# Main_EDA_-.net
KiCad netlist of a schematic drawn in Altium Designer
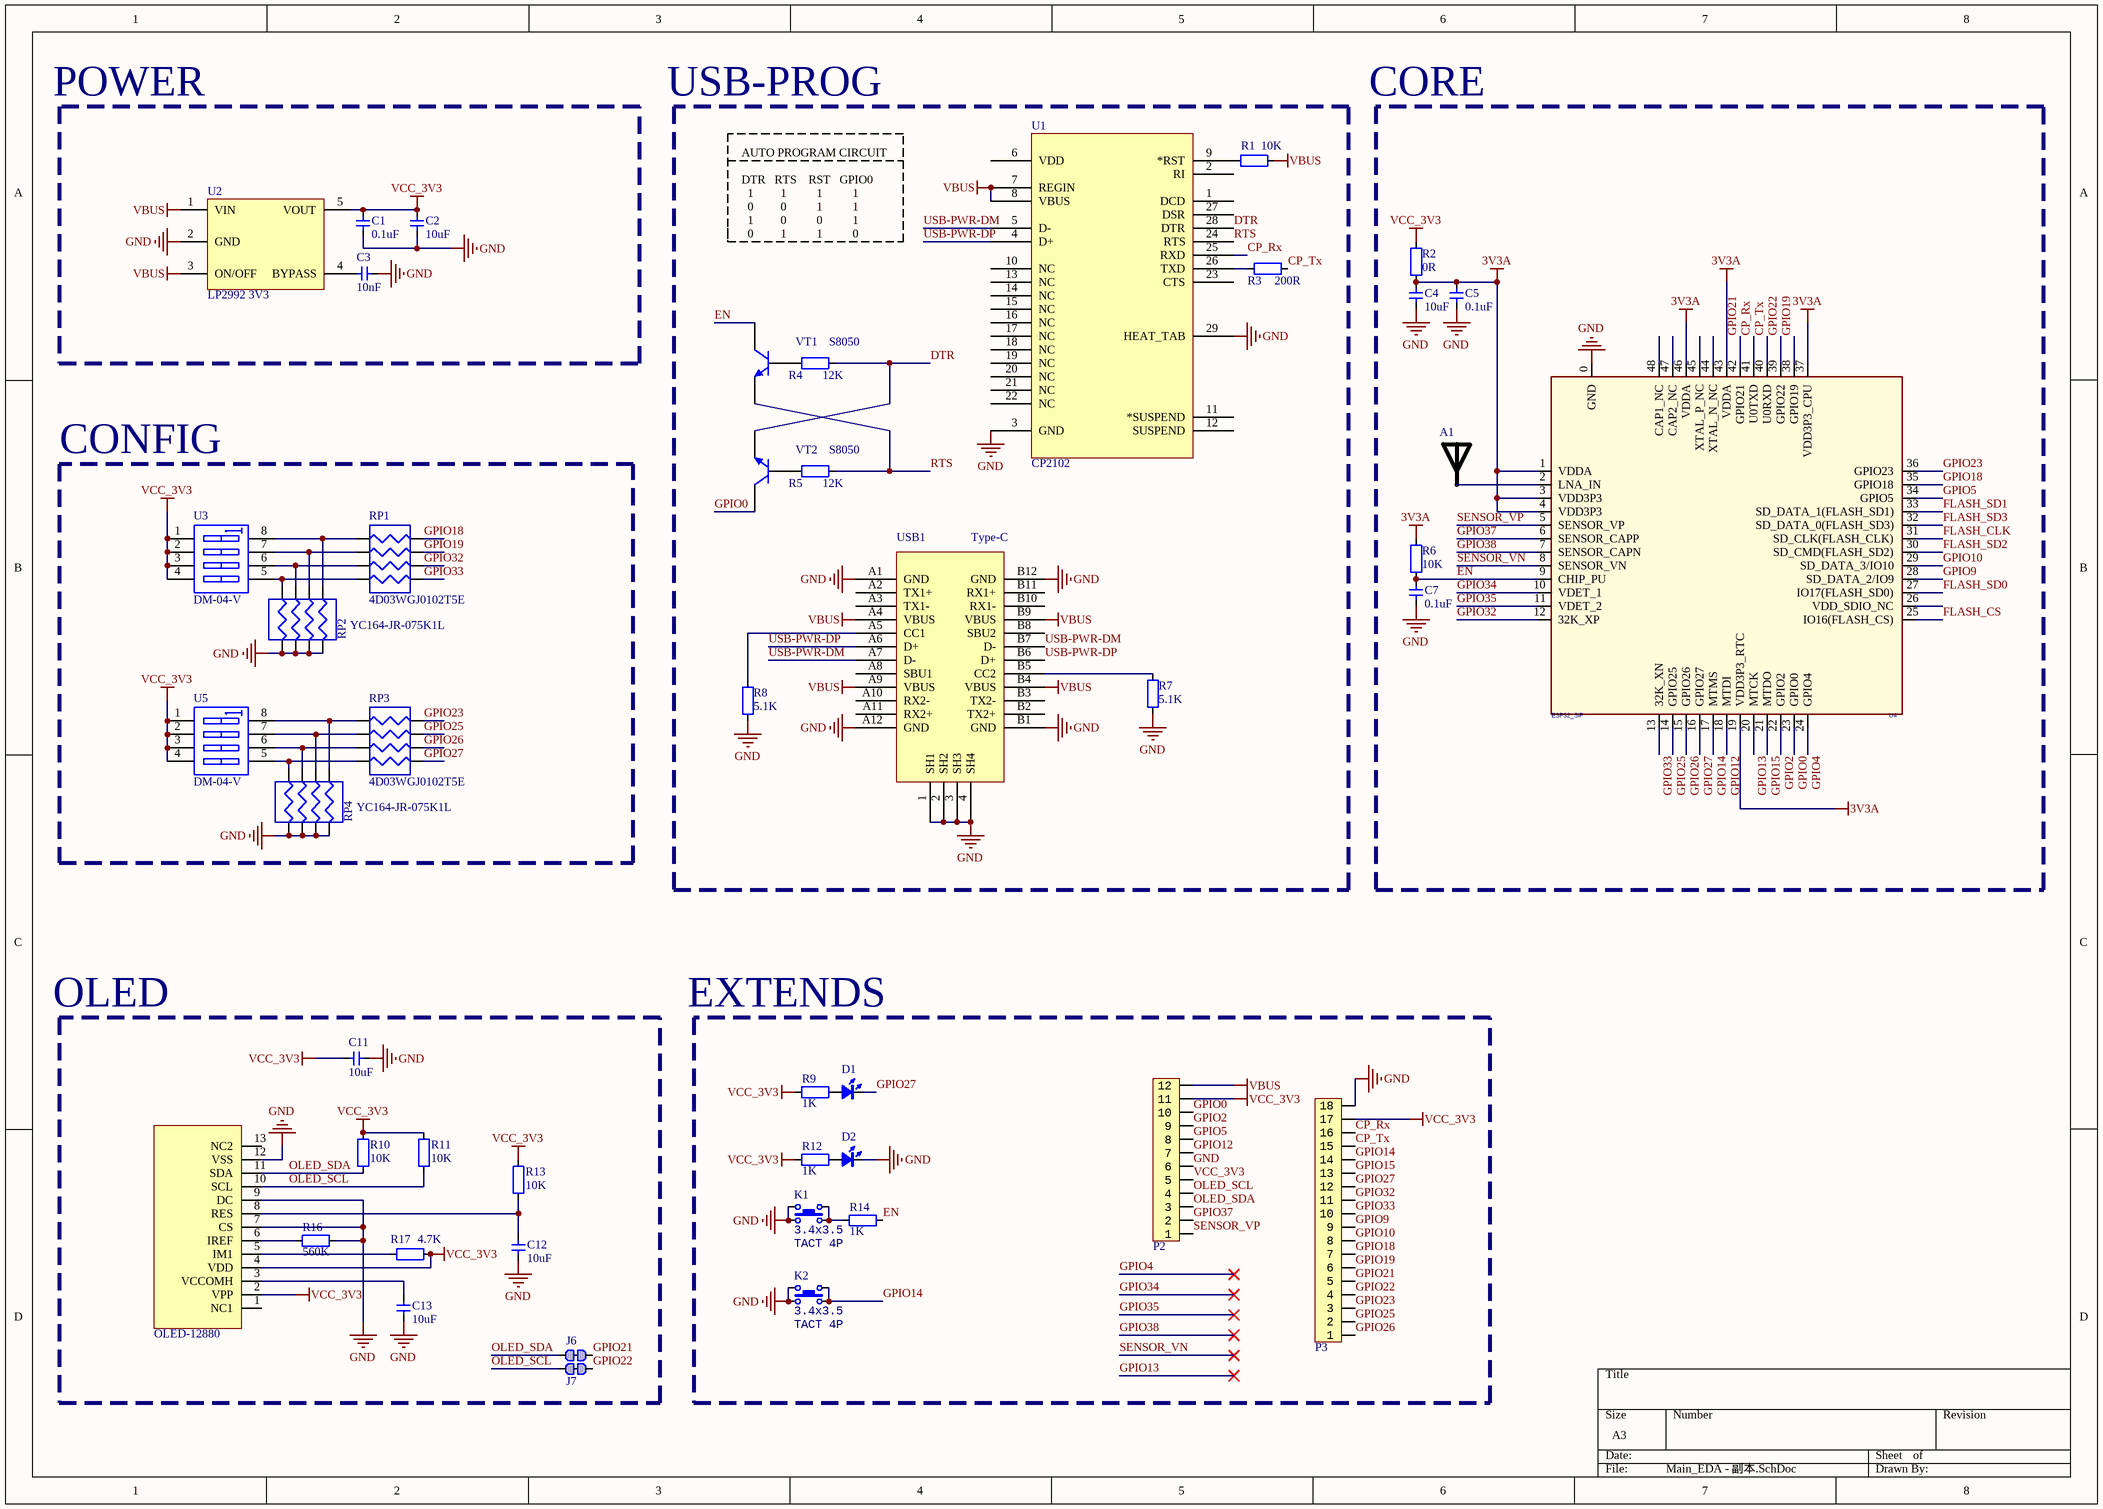
[diagram p0: Main_EDA - 副本.SchDoc]

(export (version "E")
  (design (tool "Eeschema 10.0.6"))
  (components
    (comp (ref "1")
      (value "OLED-12880")
      (footprint "OLED-12880")
      (libsource (lib "mLib") (part "OLED-12880"))
    )
    (comp (ref "A1")
      (value "RAINSUN")
      (footprint "ANT-Rainsun-AN5120")
      (libsource (lib "MyPcbLib") (part "ANT-Rainsun-AP5120"))
    )
    (comp (ref "C1")
      (value "0.1uF")
      (footprint "CAP_0402")
      (description "Capacitor")
      (libsource (lib "MyPcbLib") (part "电容-0402"))
    )
    (comp (ref "C2")
      (value "10uF")
      (footprint "CAP_0402")
      (description "Capacitor")
      (libsource (lib "MyPcbLib") (part "电容-0402"))
    )
    (comp (ref "C3")
      (value "10nF")
      (footprint "CAP_0402")
      (description "Capacitor")
      (libsource (lib "MyPcbLib") (part "电容-0402"))
    )
    (comp (ref "C4")
      (value "10uF")
      (footprint "CAP_0402")
      (description "Capacitor")
      (libsource (lib "MyPcbLib") (part "电容-0402"))
    )
    (comp (ref "C5")
      (value "0.1uF")
      (footprint "CAP_0402")
      (description "Capacitor")
      (libsource (lib "MyPcbLib") (part "电容-0402"))
    )
    (comp (ref "C7")
      (value "0.1uF")
      (footprint "CAP_0402")
      (description "Capacitor")
      (libsource (lib "MyPcbLib") (part "电容-0402"))
    )
    (comp (ref "C11")
      (value "10uF")
      (footprint "CAP_0402")
      (description "Capacitor")
      (libsource (lib "MyPcbLib") (part "电容-0402"))
    )
    (comp (ref "C12")
      (value "10uF")
      (footprint "CAP_0402")
      (description "Capacitor")
      (libsource (lib "MyPcbLib") (part "电容-0402"))
    )
    (comp (ref "C13")
      (value "10uF")
      (footprint "CAP_0402")
      (description "Capacitor")
      (libsource (lib "MyPcbLib") (part "电容-0402"))
    )
    (comp (ref "D1")
      (value "color?")
      (footprint "LED_0402_RED")
      (description "LED")
      (libsource (lib "KitSprout") (part "LED_0402"))
    )
    (comp (ref "D2")
      (value "color?")
      (footprint "LED_0402_RED")
      (description "LED")
      (libsource (lib "KitSprout") (part "LED_0402"))
    )
    (comp (ref "J6")
      (value "跳线")
      (footprint "0402-0R")
      (description "Resistor")
      (fields (field (name "PUBLISHER") "Altium Limited"))
      (libsource (lib "MyPcbLib") (part "跳线"))
    )
    (comp (ref "J7")
      (value "跳线")
      (footprint "0402-0R")
      (description "Resistor")
      (fields (field (name "PUBLISHER") "Altium Limited"))
      (libsource (lib "MyPcbLib") (part "跳线"))
    )
    (comp (ref "K1")
      (value "3.4x3.5")
      (footprint "ButtonTACT_3.5*3.55_90")
      (description "Button")
      (fields (field (name "TYPE") "TACT 4P") (field (name "Comment") "TACT 4P"))
      (libsource (lib "KitSprout") (part "ButtonTACT"))
    )
    (comp (ref "K2")
      (value "3.4x3.5")
      (footprint "ButtonTACT_3.5*3.55_90")
      (description "Button")
      (fields (field (name "TYPE") "TACT 4P") (field (name "Comment") "TACT 4P"))
      (libsource (lib "KitSprout") (part "ButtonTACT"))
    )
    (comp (ref "P2")
      (value "HDR1x12_2.54")
      (footprint "HDR1X12_2.54_180")
      (description "Header")
      (libsource (lib "KitSprout") (part "HDR1x12_2.54"))
    )
    (comp (ref "P3")
      (value "HDR1x18_2.54")
      (footprint "HDR1X18_2.54_180")
      (description "Header")
      (libsource (lib "KitSprout") (part "HDR1x18_2.54"))
    )
    (comp (ref "R1")
      (value "10K")
      (footprint "RES_0402")
      (description "Resistor")
      (libsource (lib "") (part "电阻-0402_3"))
    )
    (comp (ref "R2")
      (value "0R")
      (footprint "RES_0402")
      (description "Resistor")
      (libsource (lib "") (part "电阻-0402_1"))
    )
    (comp (ref "R3")
      (value "200R")
      (footprint "RES_0402")
      (description "Resistor")
      (libsource (lib "") (part "电阻-0402_3"))
    )
    (comp (ref "R4")
      (value "12K")
      (footprint "RES_0402")
      (description "Resistor")
      (libsource (lib "") (part "电阻-0402_3"))
    )
    (comp (ref "R5")
      (value "12K")
      (footprint "RES_0402")
      (description "Resistor")
      (libsource (lib "") (part "电阻-0402_3"))
    )
    (comp (ref "R6")
      (value "10K")
      (footprint "RES_0402")
      (description "Resistor")
      (libsource (lib "") (part "电阻-0402_1"))
    )
    (comp (ref "R7")
      (value "5.1K")
      (footprint "RES_0402")
      (description "Resistor")
      (libsource (lib "") (part "电阻-0402_1"))
    )
    (comp (ref "R8")
      (value "5.1K")
      (footprint "RES_0402")
      (description "Resistor")
      (libsource (lib "") (part "电阻-0402_1"))
    )
    (comp (ref "R9")
      (value "1K")
      (footprint "RES_0402")
      (description "Resistor")
      (libsource (lib "") (part "电阻-0402_2"))
    )
    (comp (ref "R10")
      (value "10K")
      (footprint "RES_0402")
      (description "Resistor")
      (libsource (lib "MyPcbLib") (part "电阻-0402"))
    )
    (comp (ref "R11")
      (value "10K")
      (footprint "RES_0402")
      (description "Resistor")
      (libsource (lib "MyPcbLib") (part "电阻-0402"))
    )
    (comp (ref "R12")
      (value "1K")
      (footprint "RES_0402")
      (description "Resistor")
      (libsource (lib "") (part "电阻-0402_2"))
    )
    (comp (ref "R13")
      (value "10K")
      (footprint "RES_0402")
      (description "Resistor")
      (libsource (lib "MyPcbLib") (part "电阻-0402"))
    )
    (comp (ref "R14")
      (value "1K")
      (footprint "RES_0402")
      (description "Resistor")
      (libsource (lib "") (part "电阻-0402_2"))
    )
    (comp (ref "R16")
      (value "560K")
      (footprint "RES_0402")
      (description "Resistor")
      (libsource (lib "") (part "电阻-0402_2"))
    )
    (comp (ref "R17")
      (value "4.7K")
      (footprint "RES_0402")
      (description "Resistor")
      (libsource (lib "") (part "电阻-0402_2"))
    )
    (comp (ref "RP1")
      (value "4D03WGJ0102T5E")
      (footprint "RES-ARRAY-SMD_0603-8P-L3.2-W1.6-BL")
      (libsource (lib "Schlib1") (part "RP"))
    )
    (comp (ref "RP2")
      (value "YC164-JR-075K1L")
      (footprint "RES-ARRAY-SMD_0603-8P-L3.2-W1.6-BL")
      (libsource (lib "Schlib1") (part "RP"))
    )
    (comp (ref "RP3")
      (value "4D03WGJ0102T5E")
      (footprint "RES-ARRAY-SMD_0603-8P-L3.2-W1.6-BL")
      (libsource (lib "Schlib1") (part "RP"))
    )
    (comp (ref "RP4")
      (value "YC164-JR-075K1L")
      (footprint "RES-ARRAY-SMD_0603-8P-L3.2-W1.6-BL")
      (libsource (lib "Schlib1") (part "RP"))
    )
    (comp (ref "U1")
      (value "CP2102")
      (footprint "QFN-28")
      (description "USB转TTL")
      (libsource (lib "mLib") (part "CP2102"))
    )
    (comp (ref "U2")
      (value "LP2992 3V3")
      (footprint "SOT23-5")
      (description "LDO")
      (libsource (lib "MyPcbLib") (part "LP2992"))
    )
    (comp (ref "U3")
      (value "DM-04-V")
      (footprint "SW-SMD_8P-L11.1-W6.2-P2.54-LS9.8")
      (description "DIP Switch, 4 Position, SPST")
      (fields (field (name "PUBLISHER") "Altium Limited"))
      (libsource (lib "Miscellaneous Devices") (part "SW DIP-4"))
    )
    (comp (ref "U4")
      (value "ESP32_SIP")
      (footprint "QFN-48_7X7")
      (libsource (lib "MyPcbLib") (part "ESP32-PICO"))
    )
    (comp (ref "U5")
      (value "DM-04-V")
      (footprint "SW-SMD_8P-L11.1-W6.2-P2.54-LS9.8")
      (description "DIP Switch, 4 Position, SPST")
      (fields (field (name "PUBLISHER") "Altium Limited"))
      (libsource (lib "Miscellaneous Devices") (part "SW DIP-4"))
    )
    (comp (ref "USB1")
      (value "Type-C")
      (footprint "Type-C-TOP")
      (libsource (lib "MyPcbLib") (part "USB-Type-C-TOP"))
    )
    (comp (ref "VT1")
      (value "S8050")
      (footprint "SMT_TRIODE_NPN")
      (description "Surface mount NPN transistor, package SOT-23")
      (libsource (lib "MyPcbLib") (part "SMT_TRIODE_NPN"))
    )
    (comp (ref "VT2")
      (value "S8050")
      (footprint "SMT_TRIODE_NPN")
      (description "Surface mount NPN transistor, package SOT-23")
      (libsource (lib "MyPcbLib") (part "SMT_TRIODE_NPN"))
    )
  )
  (nets
    (net (code "1") (name "/CP_Rx") (class "Default")
      (node (ref "P3") (pin "16") (pinfunction "16_16") (pintype "passive"))
      (node (ref "U1") (pin "25") (pinfunction "RXD_25") (pintype "passive"))
      (node (ref "U4") (pin "41") (pinfunction "U0TXD_41") (pintype "power_in"))
    )
    (net (code "2") (name "/CP_Tx") (class "Default")
      (node (ref "P3") (pin "15") (pinfunction "15_15") (pintype "passive"))
      (node (ref "R3") (pin "1") (pinfunction "1_1") (pintype "passive"))
      (node (ref "U4") (pin "40") (pinfunction "U0RXD_40") (pintype "power_in"))
    )
    (net (code "3") (name "/DTR") (class "Default")
      (node (ref "R4") (pin "1") (pinfunction "1_1") (pintype "passive"))
      (node (ref "U1") (pin "28") (pinfunction "DTR_28") (pintype "passive"))
      (node (ref "VT2") (pin "2") (pinfunction "E_2") (pintype "passive"))
    )
    (net (code "4") (name "/EN") (class "Default")
      (node (ref "C7") (pin "1") (pinfunction "1_1") (pintype "passive"))
      (node (ref "R14") (pin "2") (pinfunction "2_2") (pintype "passive"))
      (node (ref "R6") (pin "2") (pinfunction "2_2") (pintype "passive"))
      (node (ref "U4") (pin "9") (pinfunction "CHIP_PU_9") (pintype "passive"))
      (node (ref "VT1") (pin "3") (pinfunction "C_3") (pintype "passive"))
    )
    (net (code "5") (name "/FLASH_CLK") (class "Default")
      (node (ref "U4") (pin "31") (pinfunction "SD_CLK(FLASH_CLK)_31") (pintype "passive"))
    )
    (net (code "6") (name "/FLASH_CS") (class "Default")
      (node (ref "U4") (pin "25") (pinfunction "IO16(FLASH_CS)_25") (pintype "passive"))
    )
    (net (code "7") (name "/FLASH_SD0") (class "Default")
      (node (ref "U4") (pin "27") (pinfunction "IO17(FLASH_SD0)_27") (pintype "passive"))
    )
    (net (code "8") (name "/FLASH_SD1") (class "Default")
      (node (ref "U4") (pin "33") (pinfunction "SD_DATA_1(FLASH_SD1)_33") (pintype "passive"))
    )
    (net (code "9") (name "/FLASH_SD2") (class "Default")
      (node (ref "U4") (pin "30") (pinfunction "SD_CMD(FLASH_SD2)_30") (pintype "passive"))
    )
    (net (code "10") (name "/FLASH_SD3") (class "Default")
      (node (ref "U4") (pin "32") (pinfunction "SD_DATA_0(FLASH_SD3)_32") (pintype "passive"))
    )
    (net (code "11") (name "/GPIO0") (class "Default")
      (node (ref "P2") (pin "10") (pinfunction "10_10") (pintype "passive"))
      (node (ref "U4") (pin "23") (pinfunction "GPIO0_23") (pintype "passive"))
      (node (ref "VT2") (pin "3") (pinfunction "C_3") (pintype "passive"))
    )
    (net (code "12") (name "/GPIO2") (class "Default")
      (node (ref "P2") (pin "9") (pinfunction "9_9") (pintype "passive"))
      (node (ref "U4") (pin "22") (pinfunction "GPIO2_22") (pintype "passive"))
    )
    (net (code "13") (name "/GPIO4") (class "Default")
      (node (ref "U4") (pin "24") (pinfunction "GPIO4_24") (pintype "passive+no_connect"))
    )
    (net (code "14") (name "/GPIO5") (class "Default")
      (node (ref "P2") (pin "8") (pinfunction "8_8") (pintype "passive"))
      (node (ref "U4") (pin "34") (pinfunction "GPIO5_34") (pintype "passive"))
    )
    (net (code "15") (name "/GPIO9") (class "Default")
      (node (ref "P3") (pin "9") (pinfunction "9_9") (pintype "passive"))
      (node (ref "U4") (pin "28") (pinfunction "SD_DATA_2/IO9_28") (pintype "passive"))
    )
    (net (code "16") (name "/GPIO10") (class "Default")
      (node (ref "P3") (pin "8") (pinfunction "8_8") (pintype "passive"))
      (node (ref "U4") (pin "29") (pinfunction "SD_DATA_3/IO10_29") (pintype "passive"))
    )
    (net (code "17") (name "/GPIO12") (class "Default")
      (node (ref "P2") (pin "7") (pinfunction "7_7") (pintype "passive"))
      (node (ref "U4") (pin "18") (pinfunction "MTDI_18") (pintype "passive"))
    )
    (net (code "18") (name "/GPIO13") (class "Default")
      (node (ref "U4") (pin "20") (pinfunction "MTCK_20") (pintype "passive+no_connect"))
    )
    (net (code "19") (name "/GPIO14") (class "Default")
      (node (ref "K2") (pin "2") (pinfunction "2_2") (pintype "passive"))
      (node (ref "K2") (pin "4") (pinfunction "4_4") (pintype "passive"))
      (node (ref "P3") (pin "14") (pinfunction "14_14") (pintype "passive"))
      (node (ref "U4") (pin "17") (pinfunction "MTMS_17") (pintype "passive"))
    )
    (net (code "20") (name "/GPIO15") (class "Default")
      (node (ref "P3") (pin "13") (pinfunction "13_13") (pintype "passive"))
      (node (ref "U4") (pin "21") (pinfunction "MTDO_21") (pintype "passive"))
    )
    (net (code "21") (name "/GPIO18") (class "Default")
      (node (ref "P3") (pin "7") (pinfunction "7_7") (pintype "passive"))
      (node (ref "RP1") (pin "8") (pinfunction "8_8") (pintype "passive"))
      (node (ref "U4") (pin "35") (pinfunction "GPIO18_35") (pintype "passive"))
    )
    (net (code "22") (name "/GPIO19") (class "Default")
      (node (ref "P3") (pin "6") (pinfunction "6_6") (pintype "passive"))
      (node (ref "RP1") (pin "7") (pinfunction "7_7") (pintype "passive"))
      (node (ref "U4") (pin "38") (pinfunction "GPIO19_38") (pintype "passive"))
    )
    (net (code "23") (name "/GPIO21") (class "Default")
      (node (ref "J6") (pin "2") (pinfunction "2_2") (pintype "passive"))
      (node (ref "P3") (pin "5") (pinfunction "5_5") (pintype "passive"))
      (node (ref "U4") (pin "42") (pinfunction "GPIO21_42") (pintype "passive"))
    )
    (net (code "24") (name "/GPIO22") (class "Default")
      (node (ref "J7") (pin "2") (pinfunction "2_2") (pintype "passive"))
      (node (ref "P3") (pin "4") (pinfunction "4_4") (pintype "passive"))
      (node (ref "U4") (pin "39") (pinfunction "GPIO22_39") (pintype "passive"))
    )
    (net (code "25") (name "/GPIO23") (class "Default")
      (node (ref "P3") (pin "3") (pinfunction "3_3") (pintype "passive"))
      (node (ref "RP3") (pin "8") (pinfunction "8_8") (pintype "passive"))
      (node (ref "U4") (pin "36") (pinfunction "GPIO23_36") (pintype "passive"))
    )
    (net (code "26") (name "/GPIO25") (class "Default")
      (node (ref "P3") (pin "2") (pinfunction "2_2") (pintype "passive"))
      (node (ref "RP3") (pin "7") (pinfunction "7_7") (pintype "passive"))
      (node (ref "U4") (pin "14") (pinfunction "GPIO25_14") (pintype "passive"))
    )
    (net (code "27") (name "/GPIO26") (class "Default")
      (node (ref "P3") (pin "1") (pinfunction "1_1") (pintype "passive"))
      (node (ref "RP3") (pin "6") (pinfunction "6_6") (pintype "passive"))
      (node (ref "U4") (pin "15") (pinfunction "GPIO26_15") (pintype "passive"))
    )
    (net (code "28") (name "/GPIO27") (class "Default")
      (node (ref "D1") (pin "2") (pinfunction "K_2") (pintype "passive"))
      (node (ref "P3") (pin "12") (pinfunction "12_12") (pintype "passive"))
      (node (ref "RP3") (pin "5") (pinfunction "5_5") (pintype "passive"))
      (node (ref "U4") (pin "16") (pinfunction "GPIO27_16") (pintype "passive"))
    )
    (net (code "29") (name "/GPIO32") (class "Default")
      (node (ref "P3") (pin "11") (pinfunction "11_11") (pintype "passive"))
      (node (ref "RP1") (pin "6") (pinfunction "6_6") (pintype "passive"))
      (node (ref "U4") (pin "12") (pinfunction "32K_XP_12") (pintype "passive"))
    )
    (net (code "30") (name "/GPIO33") (class "Default")
      (node (ref "P3") (pin "10") (pinfunction "10_10") (pintype "passive"))
      (node (ref "RP1") (pin "5") (pinfunction "5_5") (pintype "passive"))
      (node (ref "U4") (pin "13") (pinfunction "32K_XN_13") (pintype "passive"))
    )
    (net (code "31") (name "/GPIO34") (class "Default")
      (node (ref "U4") (pin "10") (pinfunction "VDET_1_10") (pintype "passive+no_connect"))
    )
    (net (code "32") (name "/GPIO35") (class "Default")
      (node (ref "U4") (pin "11") (pinfunction "VDET_2_11") (pintype "passive+no_connect"))
    )
    (net (code "33") (name "/GPIO37") (class "Default")
      (node (ref "P2") (pin "2") (pinfunction "2_2") (pintype "passive"))
      (node (ref "U4") (pin "6") (pinfunction "SENSOR_CAPP_6") (pintype "passive"))
    )
    (net (code "34") (name "/GPIO38") (class "Default")
      (node (ref "U4") (pin "7") (pinfunction "SENSOR_CAPN_7") (pintype "passive+no_connect"))
    )
    (net (code "35") (name "/OLED_SCL") (class "Default")
      (node (ref "1") (pin "10") (pinfunction "SCL_10") (pintype "passive"))
      (node (ref "J7") (pin "1") (pinfunction "1_1") (pintype "passive"))
      (node (ref "P2") (pin "4") (pinfunction "4_4") (pintype "passive"))
      (node (ref "R11") (pin "1") (pinfunction "1_1") (pintype "passive"))
    )
    (net (code "36") (name "/OLED_SDA") (class "Default")
      (node (ref "1") (pin "11") (pinfunction "SDA_11") (pintype "passive"))
      (node (ref "J6") (pin "1") (pinfunction "1_1") (pintype "passive"))
      (node (ref "P2") (pin "3") (pinfunction "3_3") (pintype "passive"))
      (node (ref "R10") (pin "1") (pinfunction "1_1") (pintype "passive"))
    )
    (net (code "37") (name "/RTS") (class "Default")
      (node (ref "R5") (pin "1") (pinfunction "1_1") (pintype "passive"))
      (node (ref "U1") (pin "24") (pinfunction "RTS_24") (pintype "passive"))
      (node (ref "VT1") (pin "2") (pinfunction "E_2") (pintype "passive"))
    )
    (net (code "38") (name "/SENSOR_VN") (class "Default")
      (node (ref "U4") (pin "8") (pinfunction "SENSOR_VN_8") (pintype "passive+no_connect"))
    )
    (net (code "39") (name "/SENSOR_VP") (class "Default")
      (node (ref "P2") (pin "1") (pinfunction "1_1") (pintype "passive"))
      (node (ref "U4") (pin "5") (pinfunction "SENSOR_VP_5") (pintype "passive"))
    )
    (net (code "40") (name "/USB-PWR-DM") (class "Default")
      (node (ref "U1") (pin "5") (pinfunction "D-_5") (pintype "passive"))
      (node (ref "USB1") (pin "A7") (pinfunction "D-_A7") (pintype "passive"))
      (node (ref "USB1") (pin "B7") (pinfunction "D-_B7") (pintype "passive"))
    )
    (net (code "41") (name "/USB-PWR-DP") (class "Default")
      (node (ref "U1") (pin "4") (pinfunction "D+_4") (pintype "passive"))
      (node (ref "USB1") (pin "A6") (pinfunction "D+_A6") (pintype "passive"))
      (node (ref "USB1") (pin "B6") (pinfunction "D+_B6") (pintype "passive"))
    )
    (net (code "42") (name "3V3A") (class "Default")
      (node (ref "C4") (pin "2") (pinfunction "2_2") (pintype "passive"))
      (node (ref "C5") (pin "2") (pinfunction "2_2") (pintype "passive"))
      (node (ref "R2") (pin "2") (pinfunction "2_2") (pintype "passive"))
      (node (ref "R6") (pin "1") (pinfunction "1_1") (pintype "passive"))
      (node (ref "U4") (pin "1") (pinfunction "VDDA_1") (pintype "power_in"))
      (node (ref "U4") (pin "19") (pinfunction "VDD3P3_RTC_19") (pintype "power_in"))
      (node (ref "U4") (pin "3") (pinfunction "VDD3P3_3") (pintype "power_in"))
      (node (ref "U4") (pin "37") (pinfunction "VDD3P3_CPU_37") (pintype "power_in"))
      (node (ref "U4") (pin "4") (pinfunction "VDD3P3_4") (pintype "power_in"))
      (node (ref "U4") (pin "43") (pinfunction "VDDA_43") (pintype "power_in"))
      (node (ref "U4") (pin "46") (pinfunction "VDDA_46") (pintype "power_in"))
    )
    (net (code "43") (name "GND") (class "Default")
      (node (ref "1") (pin "12") (pinfunction "VSS_12") (pintype "passive"))
      (node (ref "1") (pin "7") (pinfunction "CS_7") (pintype "passive"))
      (node (ref "1") (pin "9") (pinfunction "DC_9") (pintype "passive"))
      (node (ref "C1") (pin "1") (pinfunction "1_1") (pintype "passive"))
      (node (ref "C11") (pin "1") (pinfunction "1_1") (pintype "passive"))
      (node (ref "C12") (pin "1") (pinfunction "1_1") (pintype "passive"))
      (node (ref "C13") (pin "1") (pinfunction "1_1") (pintype "passive"))
      (node (ref "C2") (pin "1") (pinfunction "1_1") (pintype "passive"))
      (node (ref "C3") (pin "1") (pinfunction "1_1") (pintype "passive"))
      (node (ref "C4") (pin "1") (pinfunction "1_1") (pintype "passive"))
      (node (ref "C5") (pin "1") (pinfunction "1_1") (pintype "passive"))
      (node (ref "C7") (pin "2") (pinfunction "2_2") (pintype "passive"))
      (node (ref "D2") (pin "2") (pinfunction "K_2") (pintype "passive"))
      (node (ref "K1") (pin "1") (pinfunction "1_1") (pintype "passive"))
      (node (ref "K1") (pin "3") (pinfunction "3_3") (pintype "passive"))
      (node (ref "K2") (pin "1") (pinfunction "1_1") (pintype "passive"))
      (node (ref "K2") (pin "3") (pinfunction "3_3") (pintype "passive"))
      (node (ref "P2") (pin "6") (pinfunction "6_6") (pintype "passive"))
      (node (ref "P3") (pin "18") (pinfunction "18_18") (pintype "passive"))
      (node (ref "R16") (pin "2") (pinfunction "2_2") (pintype "passive"))
      (node (ref "R7") (pin "2") (pinfunction "2_2") (pintype "passive"))
      (node (ref "R8") (pin "2") (pinfunction "2_2") (pintype "passive"))
      (node (ref "RP2") (pin "5") (pinfunction "5_5") (pintype "passive"))
      (node (ref "RP2") (pin "6") (pinfunction "6_6") (pintype "passive"))
      (node (ref "RP2") (pin "7") (pinfunction "7_7") (pintype "passive"))
      (node (ref "RP2") (pin "8") (pinfunction "8_8") (pintype "passive"))
      (node (ref "RP4") (pin "5") (pinfunction "5_5") (pintype "passive"))
      (node (ref "RP4") (pin "6") (pinfunction "6_6") (pintype "passive"))
      (node (ref "RP4") (pin "7") (pinfunction "7_7") (pintype "passive"))
      (node (ref "RP4") (pin "8") (pinfunction "8_8") (pintype "passive"))
      (node (ref "U1") (pin "29") (pinfunction "HEAT_TAB_29") (pintype "passive"))
      (node (ref "U1") (pin "3") (pinfunction "GND_3") (pintype "passive"))
      (node (ref "U2") (pin "2") (pinfunction "GND_2") (pintype "passive"))
      (node (ref "U4") (pin "0") (pinfunction "GND_0") (pintype "power_in"))
      (node (ref "USB1") (pin "1") (pinfunction "SH1_1") (pintype "passive"))
      (node (ref "USB1") (pin "2") (pinfunction "SH2_2") (pintype "passive"))
      (node (ref "USB1") (pin "3") (pinfunction "SH3_3") (pintype "passive"))
      (node (ref "USB1") (pin "4") (pinfunction "SH4_4") (pintype "passive"))
      (node (ref "USB1") (pin "A1") (pinfunction "GND_A1") (pintype "passive"))
      (node (ref "USB1") (pin "A12") (pinfunction "GND_A12") (pintype "passive"))
      (node (ref "USB1") (pin "B1") (pinfunction "GND_B1") (pintype "passive"))
      (node (ref "USB1") (pin "B12") (pinfunction "GND_B12") (pintype "passive"))
    )
    (net (code "44") (name "Net-(1-IM1)") (class "Default")
      (node (ref "1") (pin "5") (pinfunction "IM1_5") (pintype "passive"))
      (node (ref "R17") (pin "1") (pinfunction "1_1") (pintype "passive"))
    )
    (net (code "45") (name "Net-(1-IREF)") (class "Default")
      (node (ref "1") (pin "6") (pinfunction "IREF_6") (pintype "passive"))
      (node (ref "R16") (pin "1") (pinfunction "1_1") (pintype "passive"))
    )
    (net (code "46") (name "Net-(1-RES)") (class "Default")
      (node (ref "1") (pin "8") (pinfunction "RES_8") (pintype "passive"))
      (node (ref "C12") (pin "2") (pinfunction "2_2") (pintype "passive"))
      (node (ref "R13") (pin "1") (pinfunction "1_1") (pintype "passive"))
    )
    (net (code "47") (name "Net-(1-VCCOMH)") (class "Default")
      (node (ref "1") (pin "3") (pinfunction "VCCOMH_3") (pintype "passive"))
      (node (ref "C13") (pin "2") (pinfunction "2_2") (pintype "passive"))
    )
    (net (code "48") (name "Net-(D1-A)") (class "Default")
      (node (ref "D1") (pin "1") (pinfunction "A_1") (pintype "passive"))
      (node (ref "R9") (pin "2") (pinfunction "2_2") (pintype "passive"))
    )
    (net (code "49") (name "Net-(D2-A)") (class "Default")
      (node (ref "D2") (pin "1") (pinfunction "A_1") (pintype "passive"))
      (node (ref "R12") (pin "2") (pinfunction "2_2") (pintype "passive"))
    )
    (net (code "50") (name "Net-(K1-Pad2)") (class "Default")
      (node (ref "K1") (pin "2") (pinfunction "2_2") (pintype "passive"))
      (node (ref "K1") (pin "4") (pinfunction "4_4") (pintype "passive"))
      (node (ref "R14") (pin "1") (pinfunction "1_1") (pintype "passive"))
    )
    (net (code "51") (name "Net-(U1-*RST)") (class "Default")
      (node (ref "R1") (pin "2") (pinfunction "2_2") (pintype "passive"))
      (node (ref "U1") (pin "9") (pinfunction "*RST_9") (pintype "passive"))
    )
    (net (code "52") (name "Net-(U1-TXD)") (class "Default")
      (node (ref "R3") (pin "2") (pinfunction "2_2") (pintype "passive"))
      (node (ref "U1") (pin "26") (pinfunction "TXD_26") (pintype "passive"))
    )
    (net (code "53") (name "Net-(U2-BYPASS)") (class "Default")
      (node (ref "C3") (pin "2") (pinfunction "2_2") (pintype "passive"))
      (node (ref "U2") (pin "4") (pinfunction "BYPASS_4") (pintype "passive"))
    )
    (net (code "54") (name "Net-(U3-B1)") (class "Default")
      (node (ref "RP1") (pin "1") (pinfunction "1_1") (pintype "passive"))
      (node (ref "RP2") (pin "1") (pinfunction "1_1") (pintype "passive"))
      (node (ref "U3") (pin "8") (pinfunction "B1_8") (pintype "passive"))
    )
    (net (code "55") (name "Net-(U3-B2)") (class "Default")
      (node (ref "RP1") (pin "2") (pinfunction "2_2") (pintype "passive"))
      (node (ref "RP2") (pin "2") (pinfunction "2_2") (pintype "passive"))
      (node (ref "U3") (pin "7") (pinfunction "B2_7") (pintype "passive"))
    )
    (net (code "56") (name "Net-(U3-B3)") (class "Default")
      (node (ref "RP1") (pin "3") (pinfunction "3_3") (pintype "passive"))
      (node (ref "RP2") (pin "3") (pinfunction "3_3") (pintype "passive"))
      (node (ref "U3") (pin "6") (pinfunction "B3_6") (pintype "passive"))
    )
    (net (code "57") (name "Net-(U3-B4)") (class "Default")
      (node (ref "RP1") (pin "4") (pinfunction "4_4") (pintype "passive"))
      (node (ref "RP2") (pin "4") (pinfunction "4_4") (pintype "passive"))
      (node (ref "U3") (pin "5") (pinfunction "B4_5") (pintype "passive"))
    )
    (net (code "58") (name "Net-(U4-LNA_IN)") (class "Default")
      (node (ref "A1") (pin "1") (pinfunction "1_1") (pintype "passive"))
      (node (ref "U4") (pin "2") (pinfunction "LNA_IN_2") (pintype "passive"))
    )
    (net (code "59") (name "Net-(U5-B1)") (class "Default")
      (node (ref "RP3") (pin "1") (pinfunction "1_1") (pintype "passive"))
      (node (ref "RP4") (pin "1") (pinfunction "1_1") (pintype "passive"))
      (node (ref "U5") (pin "8") (pinfunction "B1_8") (pintype "passive"))
    )
    (net (code "60") (name "Net-(U5-B2)") (class "Default")
      (node (ref "RP3") (pin "2") (pinfunction "2_2") (pintype "passive"))
      (node (ref "RP4") (pin "2") (pinfunction "2_2") (pintype "passive"))
      (node (ref "U5") (pin "7") (pinfunction "B2_7") (pintype "passive"))
    )
    (net (code "61") (name "Net-(U5-B3)") (class "Default")
      (node (ref "RP3") (pin "3") (pinfunction "3_3") (pintype "passive"))
      (node (ref "RP4") (pin "3") (pinfunction "3_3") (pintype "passive"))
      (node (ref "U5") (pin "6") (pinfunction "B3_6") (pintype "passive"))
    )
    (net (code "62") (name "Net-(U5-B4)") (class "Default")
      (node (ref "RP3") (pin "4") (pinfunction "4_4") (pintype "passive"))
      (node (ref "RP4") (pin "4") (pinfunction "4_4") (pintype "passive"))
      (node (ref "U5") (pin "5") (pinfunction "B4_5") (pintype "passive"))
    )
    (net (code "63") (name "Net-(USB1-CC1)") (class "Default")
      (node (ref "R8") (pin "1") (pinfunction "1_1") (pintype "passive"))
      (node (ref "USB1") (pin "A5") (pinfunction "CC1_A5") (pintype "passive"))
    )
    (net (code "64") (name "Net-(USB1-CC2)") (class "Default")
      (node (ref "R7") (pin "1") (pinfunction "1_1") (pintype "passive"))
      (node (ref "USB1") (pin "B5") (pinfunction "CC2_B5") (pintype "passive"))
    )
    (net (code "65") (name "Net-(VT1-B)") (class "Default")
      (node (ref "R4") (pin "2") (pinfunction "2_2") (pintype "passive"))
      (node (ref "VT1") (pin "1") (pinfunction "B_1") (pintype "passive"))
    )
    (net (code "66") (name "Net-(VT2-B)") (class "Default")
      (node (ref "R5") (pin "2") (pinfunction "2_2") (pintype "passive"))
      (node (ref "VT2") (pin "1") (pinfunction "B_1") (pintype "passive"))
    )
    (net (code "67") (name "VBUS") (class "Default")
      (node (ref "P2") (pin "12") (pinfunction "12_12") (pintype "passive"))
      (node (ref "R1") (pin "1") (pinfunction "1_1") (pintype "passive"))
      (node (ref "U1") (pin "7") (pinfunction "REGIN_7") (pintype "passive"))
      (node (ref "U1") (pin "8") (pinfunction "VBUS_8") (pintype "passive"))
      (node (ref "U2") (pin "1") (pinfunction "VIN_1") (pintype "passive"))
      (node (ref "U2") (pin "3") (pinfunction "ON/OFF_3") (pintype "passive"))
      (node (ref "USB1") (pin "A4") (pinfunction "VBUS_A4") (pintype "passive"))
      (node (ref "USB1") (pin "A9") (pinfunction "VBUS_A9") (pintype "passive"))
      (node (ref "USB1") (pin "B4") (pinfunction "VBUS_B4") (pintype "passive"))
      (node (ref "USB1") (pin "B9") (pinfunction "VBUS_B9") (pintype "passive"))
    )
    (net (code "68") (name "VCC_3V3") (class "Default")
      (node (ref "1") (pin "2") (pinfunction "VPP_2") (pintype "passive"))
      (node (ref "1") (pin "4") (pinfunction "VDD_4") (pintype "passive"))
      (node (ref "C1") (pin "2") (pinfunction "2_2") (pintype "passive"))
      (node (ref "C11") (pin "2") (pinfunction "2_2") (pintype "passive"))
      (node (ref "C2") (pin "2") (pinfunction "2_2") (pintype "passive"))
      (node (ref "P2") (pin "11") (pinfunction "11_11") (pintype "passive"))
      (node (ref "P2") (pin "5") (pinfunction "5_5") (pintype "passive"))
      (node (ref "P3") (pin "17") (pinfunction "17_17") (pintype "passive"))
      (node (ref "R10") (pin "2") (pinfunction "2_2") (pintype "passive"))
      (node (ref "R11") (pin "2") (pinfunction "2_2") (pintype "passive"))
      (node (ref "R12") (pin "1") (pinfunction "1_1") (pintype "passive"))
      (node (ref "R13") (pin "2") (pinfunction "2_2") (pintype "passive"))
      (node (ref "R17") (pin "2") (pinfunction "2_2") (pintype "passive"))
      (node (ref "R2") (pin "1") (pinfunction "1_1") (pintype "passive"))
      (node (ref "R9") (pin "1") (pinfunction "1_1") (pintype "passive"))
      (node (ref "U2") (pin "5") (pinfunction "VOUT_5") (pintype "passive"))
      (node (ref "U3") (pin "1") (pinfunction "A1_1") (pintype "passive"))
      (node (ref "U3") (pin "2") (pinfunction "A2_2") (pintype "passive"))
      (node (ref "U3") (pin "3") (pinfunction "A3_3") (pintype "passive"))
      (node (ref "U3") (pin "4") (pinfunction "A4_4") (pintype "passive"))
      (node (ref "U5") (pin "1") (pinfunction "A1_1") (pintype "passive"))
      (node (ref "U5") (pin "2") (pinfunction "A2_2") (pintype "passive"))
      (node (ref "U5") (pin "3") (pinfunction "A3_3") (pintype "passive"))
      (node (ref "U5") (pin "4") (pinfunction "A4_4") (pintype "passive"))
    )
    (net (code "69") (name "unconnected-(1-NC1-Pad1)") (class "Default")
      (node (ref "1") (pin "1") (pinfunction "NC1_1") (pintype "passive"))
    )
    (net (code "70") (name "unconnected-(1-NC2-Pad13)") (class "Default")
      (node (ref "1") (pin "13") (pinfunction "NC2_13") (pintype "passive"))
    )
    (net (code "71") (name "unconnected-(U1-*SUSPEND-Pad11)") (class "Default")
      (node (ref "U1") (pin "11") (pinfunction "*SUSPEND_11") (pintype "passive"))
    )
    (net (code "72") (name "unconnected-(U1-CTS-Pad23)") (class "Default")
      (node (ref "U1") (pin "23") (pinfunction "CTS_23") (pintype "passive"))
    )
    (net (code "73") (name "unconnected-(U1-DCD-Pad1)") (class "Default")
      (node (ref "U1") (pin "1") (pinfunction "DCD_1") (pintype "passive"))
    )
    (net (code "74") (name "unconnected-(U1-DSR-Pad27)") (class "Default")
      (node (ref "U1") (pin "27") (pinfunction "DSR_27") (pintype "passive"))
    )
    (net (code "75") (name "unconnected-(U1-NC-Pad10)") (class "Default")
      (node (ref "U1") (pin "10") (pinfunction "NC_10") (pintype "passive"))
    )
    (net (code "76") (name "unconnected-(U1-NC-Pad13)") (class "Default")
      (node (ref "U1") (pin "13") (pinfunction "NC_13") (pintype "passive"))
    )
    (net (code "77") (name "unconnected-(U1-NC-Pad14)") (class "Default")
      (node (ref "U1") (pin "14") (pinfunction "NC_14") (pintype "passive"))
    )
    (net (code "78") (name "unconnected-(U1-NC-Pad15)") (class "Default")
      (node (ref "U1") (pin "15") (pinfunction "NC_15") (pintype "passive"))
    )
    (net (code "79") (name "unconnected-(U1-NC-Pad16)") (class "Default")
      (node (ref "U1") (pin "16") (pinfunction "NC_16") (pintype "passive"))
    )
    (net (code "80") (name "unconnected-(U1-NC-Pad17)") (class "Default")
      (node (ref "U1") (pin "17") (pinfunction "NC_17") (pintype "passive"))
    )
    (net (code "81") (name "unconnected-(U1-NC-Pad18)") (class "Default")
      (node (ref "U1") (pin "18") (pinfunction "NC_18") (pintype "passive"))
    )
    (net (code "82") (name "unconnected-(U1-NC-Pad19)") (class "Default")
      (node (ref "U1") (pin "19") (pinfunction "NC_19") (pintype "passive"))
    )
    (net (code "83") (name "unconnected-(U1-NC-Pad20)") (class "Default")
      (node (ref "U1") (pin "20") (pinfunction "NC_20") (pintype "passive"))
    )
    (net (code "84") (name "unconnected-(U1-NC-Pad21)") (class "Default")
      (node (ref "U1") (pin "21") (pinfunction "NC_21") (pintype "passive"))
    )
    (net (code "85") (name "unconnected-(U1-NC-Pad22)") (class "Default")
      (node (ref "U1") (pin "22") (pinfunction "NC_22") (pintype "passive"))
    )
    (net (code "86") (name "unconnected-(U1-RI-Pad2)") (class "Default")
      (node (ref "U1") (pin "2") (pinfunction "RI_2") (pintype "passive"))
    )
    (net (code "87") (name "unconnected-(U1-SUSPEND-Pad12)") (class "Default")
      (node (ref "U1") (pin "12") (pinfunction "SUSPEND_12") (pintype "passive"))
    )
    (net (code "88") (name "unconnected-(U1-VDD-Pad6)") (class "Default")
      (node (ref "U1") (pin "6") (pinfunction "VDD_6") (pintype "passive"))
    )
    (net (code "89") (name "unconnected-(U4-CAP1_NC-Pad48)") (class "Default")
      (node (ref "U4") (pin "48") (pinfunction "CAP1_NC_48") (pintype "passive"))
    )
    (net (code "90") (name "unconnected-(U4-CAP2_NC-Pad47)") (class "Default")
      (node (ref "U4") (pin "47") (pinfunction "CAP2_NC_47") (pintype "passive"))
    )
    (net (code "91") (name "unconnected-(U4-VDD_SDIO_NC-Pad26)") (class "Default")
      (node (ref "U4") (pin "26") (pinfunction "VDD_SDIO_NC_26") (pintype "passive"))
    )
    (net (code "92") (name "unconnected-(U4-XTAL_N_NC-Pad44)") (class "Default")
      (node (ref "U4") (pin "44") (pinfunction "XTAL_N_NC_44") (pintype "passive"))
    )
    (net (code "93") (name "unconnected-(U4-XTAL_P_NC-Pad45)") (class "Default")
      (node (ref "U4") (pin "45") (pinfunction "XTAL_P_NC_45") (pintype "passive"))
    )
    (net (code "94") (name "unconnected-(USB1-RX1+-PadB11)") (class "Default")
      (node (ref "USB1") (pin "B11") (pinfunction "RX1+_B11") (pintype "passive"))
    )
    (net (code "95") (name "unconnected-(USB1-RX1--PadB10)") (class "Default")
      (node (ref "USB1") (pin "B10") (pinfunction "RX1-_B10") (pintype "passive"))
    )
    (net (code "96") (name "unconnected-(USB1-RX2+-PadA11)") (class "Default")
      (node (ref "USB1") (pin "A11") (pinfunction "RX2+_A11") (pintype "passive"))
    )
    (net (code "97") (name "unconnected-(USB1-RX2--PadA10)") (class "Default")
      (node (ref "USB1") (pin "A10") (pinfunction "RX2-_A10") (pintype "passive"))
    )
    (net (code "98") (name "unconnected-(USB1-SBU1-PadA8)") (class "Default")
      (node (ref "USB1") (pin "A8") (pinfunction "SBU1_A8") (pintype "passive"))
    )
    (net (code "99") (name "unconnected-(USB1-SBU2-PadB8)") (class "Default")
      (node (ref "USB1") (pin "B8") (pinfunction "SBU2_B8") (pintype "passive"))
    )
    (net (code "100") (name "unconnected-(USB1-TX1+-PadA2)") (class "Default")
      (node (ref "USB1") (pin "A2") (pinfunction "TX1+_A2") (pintype "passive"))
    )
    (net (code "101") (name "unconnected-(USB1-TX1--PadA3)") (class "Default")
      (node (ref "USB1") (pin "A3") (pinfunction "TX1-_A3") (pintype "passive"))
    )
    (net (code "102") (name "unconnected-(USB1-TX2+-PadB2)") (class "Default")
      (node (ref "USB1") (pin "B2") (pinfunction "TX2+_B2") (pintype "passive"))
    )
    (net (code "103") (name "unconnected-(USB1-TX2--PadB3)") (class "Default")
      (node (ref "USB1") (pin "B3") (pinfunction "TX2-_B3") (pintype "passive"))
    )
  )
)
